# FPGA1_PWR.net
KiCad netlist of a schematic drawn in Altium Designer
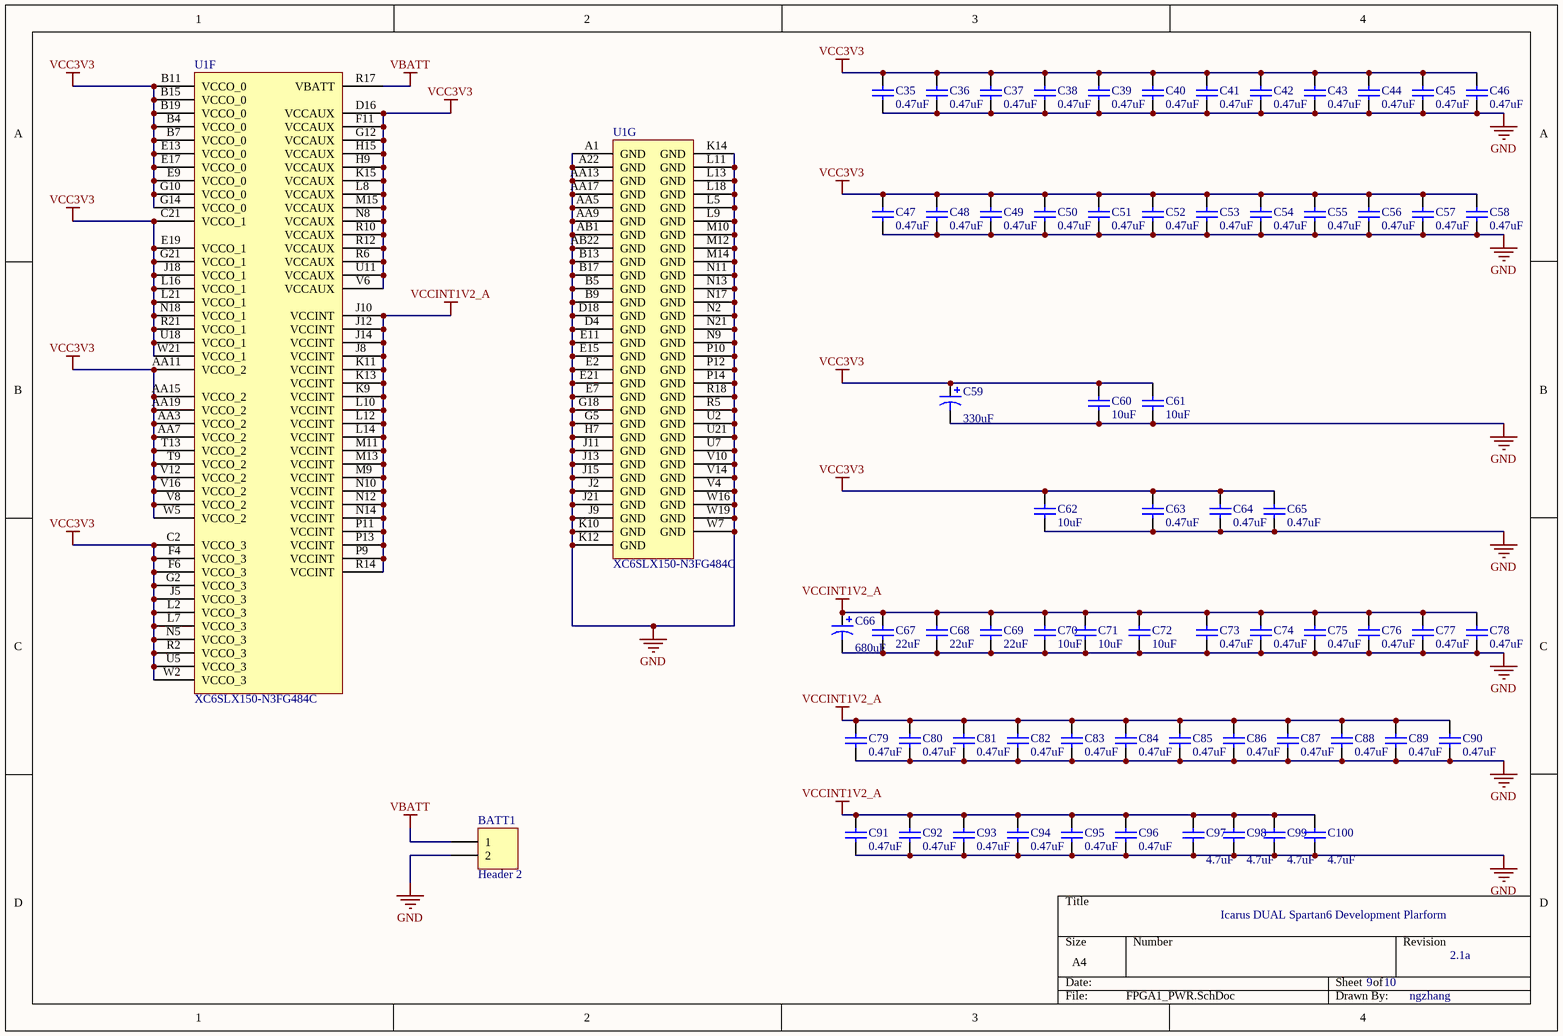
[diagram p0: FPGA1_PWR.SchDoc]

(export (version "E")
  (design (tool "Eeschema 10.0.6"))
  (components
    (comp (ref "BATT1")
      (value "Header 2")
      (footprint "HDR1X2")
      (description "Header, 2-Pin")
      (fields (field (name "PUBLISHER") "Altium Limited"))
      (libsource (lib "Miscellaneous Connectors") (part "Header 2"))
    )
    (comp (ref "C35")
      (value "0.47uF")
      (footprint "BGA0402")
      (description "Capacitor (Semiconductor SIM Model)")
      (fields (field (name "PUBLISHER") "Altium Limited"))
      (libsource (lib "Miscellaneous Devices") (part "Cap Semi"))
    )
    (comp (ref "C36")
      (value "0.47uF")
      (footprint "BGA0402")
      (description "Capacitor (Semiconductor SIM Model)")
      (fields (field (name "PUBLISHER") "Altium Limited"))
      (libsource (lib "Miscellaneous Devices") (part "Cap Semi"))
    )
    (comp (ref "C37")
      (value "0.47uF")
      (footprint "BGA0402")
      (description "Capacitor (Semiconductor SIM Model)")
      (fields (field (name "PUBLISHER") "Altium Limited"))
      (libsource (lib "Miscellaneous Devices") (part "Cap Semi"))
    )
    (comp (ref "C38")
      (value "0.47uF")
      (footprint "BGA0402")
      (description "Capacitor (Semiconductor SIM Model)")
      (fields (field (name "PUBLISHER") "Altium Limited"))
      (libsource (lib "Miscellaneous Devices") (part "Cap Semi"))
    )
    (comp (ref "C39")
      (value "0.47uF")
      (footprint "BGA0402")
      (description "Capacitor (Semiconductor SIM Model)")
      (fields (field (name "PUBLISHER") "Altium Limited"))
      (libsource (lib "Miscellaneous Devices") (part "Cap Semi"))
    )
    (comp (ref "C40")
      (value "0.47uF")
      (footprint "BGA0402")
      (description "Capacitor (Semiconductor SIM Model)")
      (fields (field (name "PUBLISHER") "Altium Limited"))
      (libsource (lib "Miscellaneous Devices") (part "Cap Semi"))
    )
    (comp (ref "C41")
      (value "0.47uF")
      (footprint "BGA0402")
      (description "Capacitor (Semiconductor SIM Model)")
      (fields (field (name "PUBLISHER") "Altium Limited"))
      (libsource (lib "Miscellaneous Devices") (part "Cap Semi"))
    )
    (comp (ref "C42")
      (value "0.47uF")
      (footprint "BGA0402")
      (description "Capacitor (Semiconductor SIM Model)")
      (fields (field (name "PUBLISHER") "Altium Limited"))
      (libsource (lib "Miscellaneous Devices") (part "Cap Semi"))
    )
    (comp (ref "C43")
      (value "0.47uF")
      (footprint "BGA0402")
      (description "Capacitor (Semiconductor SIM Model)")
      (fields (field (name "PUBLISHER") "Altium Limited"))
      (libsource (lib "Miscellaneous Devices") (part "Cap Semi"))
    )
    (comp (ref "C44")
      (value "0.47uF")
      (footprint "BGA0402")
      (description "Capacitor (Semiconductor SIM Model)")
      (fields (field (name "PUBLISHER") "Altium Limited"))
      (libsource (lib "Miscellaneous Devices") (part "Cap Semi"))
    )
    (comp (ref "C45")
      (value "0.47uF")
      (footprint "BGA0402")
      (description "Capacitor (Semiconductor SIM Model)")
      (fields (field (name "PUBLISHER") "Altium Limited"))
      (libsource (lib "Miscellaneous Devices") (part "Cap Semi"))
    )
    (comp (ref "C46")
      (value "0.47uF")
      (footprint "BGA0402")
      (description "Capacitor (Semiconductor SIM Model)")
      (fields (field (name "PUBLISHER") "Altium Limited"))
      (libsource (lib "Miscellaneous Devices") (part "Cap Semi"))
    )
    (comp (ref "C47")
      (value "0.47uF")
      (footprint "BGA0402")
      (description "Capacitor (Semiconductor SIM Model)")
      (fields (field (name "PUBLISHER") "Altium Limited"))
      (libsource (lib "Miscellaneous Devices") (part "Cap Semi"))
    )
    (comp (ref "C48")
      (value "0.47uF")
      (footprint "BGA0402")
      (description "Capacitor (Semiconductor SIM Model)")
      (fields (field (name "PUBLISHER") "Altium Limited"))
      (libsource (lib "Miscellaneous Devices") (part "Cap Semi"))
    )
    (comp (ref "C49")
      (value "0.47uF")
      (footprint "BGA0402")
      (description "Capacitor (Semiconductor SIM Model)")
      (fields (field (name "PUBLISHER") "Altium Limited"))
      (libsource (lib "Miscellaneous Devices") (part "Cap Semi"))
    )
    (comp (ref "C50")
      (value "0.47uF")
      (footprint "BGA0402")
      (description "Capacitor (Semiconductor SIM Model)")
      (fields (field (name "PUBLISHER") "Altium Limited"))
      (libsource (lib "Miscellaneous Devices") (part "Cap Semi"))
    )
    (comp (ref "C51")
      (value "0.47uF")
      (footprint "BGA0402")
      (description "Capacitor (Semiconductor SIM Model)")
      (fields (field (name "PUBLISHER") "Altium Limited"))
      (libsource (lib "Miscellaneous Devices") (part "Cap Semi"))
    )
    (comp (ref "C52")
      (value "0.47uF")
      (footprint "BGA0402")
      (description "Capacitor (Semiconductor SIM Model)")
      (fields (field (name "PUBLISHER") "Altium Limited"))
      (libsource (lib "Miscellaneous Devices") (part "Cap Semi"))
    )
    (comp (ref "C53")
      (value "0.47uF")
      (footprint "BGA0402")
      (description "Capacitor (Semiconductor SIM Model)")
      (fields (field (name "PUBLISHER") "Altium Limited"))
      (libsource (lib "Miscellaneous Devices") (part "Cap Semi"))
    )
    (comp (ref "C54")
      (value "0.47uF")
      (footprint "BGA0402")
      (description "Capacitor (Semiconductor SIM Model)")
      (fields (field (name "PUBLISHER") "Altium Limited"))
      (libsource (lib "Miscellaneous Devices") (part "Cap Semi"))
    )
    (comp (ref "C55")
      (value "0.47uF")
      (footprint "BGA0402")
      (description "Capacitor (Semiconductor SIM Model)")
      (fields (field (name "PUBLISHER") "Altium Limited"))
      (libsource (lib "Miscellaneous Devices") (part "Cap Semi"))
    )
    (comp (ref "C56")
      (value "0.47uF")
      (footprint "BGA0402")
      (description "Capacitor (Semiconductor SIM Model)")
      (fields (field (name "PUBLISHER") "Altium Limited"))
      (libsource (lib "Miscellaneous Devices") (part "Cap Semi"))
    )
    (comp (ref "C57")
      (value "0.47uF")
      (footprint "BGA0402")
      (description "Capacitor (Semiconductor SIM Model)")
      (fields (field (name "PUBLISHER") "Altium Limited"))
      (libsource (lib "Miscellaneous Devices") (part "Cap Semi"))
    )
    (comp (ref "C58")
      (value "0.47uF")
      (footprint "BGA0402")
      (description "Capacitor (Semiconductor SIM Model)")
      (fields (field (name "PUBLISHER") "Altium Limited"))
      (libsource (lib "Miscellaneous Devices") (part "Cap Semi"))
    )
    (comp (ref "C59")
      (value "330uF")
      (footprint "D")
      (description "Polarized Capacitor (Surface Mount)")
      (fields (field (name "PUBLISHER") "Altium Limited"))
      (libsource (lib "Miscellaneous Devices") (part "Cap Pol3"))
    )
    (comp (ref "C60")
      (value "10uF")
      (footprint "CAPC2012N")
      (description "Capacitor (Semiconductor SIM Model)")
      (fields (field (name "PUBLISHER") "Altium Limited"))
      (libsource (lib "Miscellaneous Devices") (part "Cap Semi"))
    )
    (comp (ref "C61")
      (value "10uF")
      (footprint "CAPC2012N")
      (description "Capacitor (Semiconductor SIM Model)")
      (fields (field (name "PUBLISHER") "Altium Limited"))
      (libsource (lib "Miscellaneous Devices") (part "Cap Semi"))
    )
    (comp (ref "C62")
      (value "10uF")
      (footprint "CAPC2012N")
      (description "Capacitor (Semiconductor SIM Model)")
      (fields (field (name "PUBLISHER") "Altium Limited"))
      (libsource (lib "Miscellaneous Devices") (part "Cap Semi"))
    )
    (comp (ref "C63")
      (value "0.47uF")
      (footprint "BGA0402")
      (description "Capacitor (Semiconductor SIM Model)")
      (fields (field (name "PUBLISHER") "Altium Limited"))
      (libsource (lib "Miscellaneous Devices") (part "Cap Semi"))
    )
    (comp (ref "C64")
      (value "0.47uF")
      (footprint "BGA0402")
      (description "Capacitor (Semiconductor SIM Model)")
      (fields (field (name "PUBLISHER") "Altium Limited"))
      (libsource (lib "Miscellaneous Devices") (part "Cap Semi"))
    )
    (comp (ref "C65")
      (value "0.47uF")
      (footprint "BGA0402")
      (description "Capacitor (Semiconductor SIM Model)")
      (fields (field (name "PUBLISHER") "Altium Limited"))
      (libsource (lib "Miscellaneous Devices") (part "Cap Semi"))
    )
    (comp (ref "C66")
      (value "680uF")
      (footprint "D")
      (description "Polarized Capacitor (Surface Mount)")
      (fields (field (name "PUBLISHER") "Altium Limited"))
      (libsource (lib "Miscellaneous Devices") (part "Cap Pol3"))
    )
    (comp (ref "C67")
      (value "22uF")
      (footprint "CAPC3216N")
      (description "Capacitor (Semiconductor SIM Model)")
      (fields (field (name "PUBLISHER") "Altium Limited"))
      (libsource (lib "Miscellaneous Devices") (part "Cap Semi"))
    )
    (comp (ref "C68")
      (value "22uF")
      (footprint "CAPC3216N")
      (description "Capacitor (Semiconductor SIM Model)")
      (fields (field (name "PUBLISHER") "Altium Limited"))
      (libsource (lib "Miscellaneous Devices") (part "Cap Semi"))
    )
    (comp (ref "C69")
      (value "22uF")
      (footprint "CAPC3216N")
      (description "Capacitor (Semiconductor SIM Model)")
      (fields (field (name "PUBLISHER") "Altium Limited"))
      (libsource (lib "Miscellaneous Devices") (part "Cap Semi"))
    )
    (comp (ref "C70")
      (value "10uF")
      (footprint "CAPC2012N")
      (description "Capacitor (Semiconductor SIM Model)")
      (fields (field (name "PUBLISHER") "Altium Limited"))
      (libsource (lib "Miscellaneous Devices") (part "Cap Semi"))
    )
    (comp (ref "C71")
      (value "10uF")
      (footprint "CAPC2012N")
      (description "Capacitor (Semiconductor SIM Model)")
      (fields (field (name "PUBLISHER") "Altium Limited"))
      (libsource (lib "Miscellaneous Devices") (part "Cap Semi"))
    )
    (comp (ref "C72")
      (value "10uF")
      (footprint "CAPC2012N")
      (description "Capacitor (Semiconductor SIM Model)")
      (fields (field (name "PUBLISHER") "Altium Limited"))
      (libsource (lib "Miscellaneous Devices") (part "Cap Semi"))
    )
    (comp (ref "C73")
      (value "0.47uF")
      (footprint "BGA0402")
      (description "Capacitor (Semiconductor SIM Model)")
      (fields (field (name "PUBLISHER") "Altium Limited"))
      (libsource (lib "Miscellaneous Devices") (part "Cap Semi"))
    )
    (comp (ref "C74")
      (value "0.47uF")
      (footprint "BGA0402")
      (description "Capacitor (Semiconductor SIM Model)")
      (fields (field (name "PUBLISHER") "Altium Limited"))
      (libsource (lib "Miscellaneous Devices") (part "Cap Semi"))
    )
    (comp (ref "C75")
      (value "0.47uF")
      (footprint "BGA0402")
      (description "Capacitor (Semiconductor SIM Model)")
      (fields (field (name "PUBLISHER") "Altium Limited"))
      (libsource (lib "Miscellaneous Devices") (part "Cap Semi"))
    )
    (comp (ref "C76")
      (value "0.47uF")
      (footprint "BGA0402")
      (description "Capacitor (Semiconductor SIM Model)")
      (fields (field (name "PUBLISHER") "Altium Limited"))
      (libsource (lib "Miscellaneous Devices") (part "Cap Semi"))
    )
    (comp (ref "C77")
      (value "0.47uF")
      (footprint "BGA0402")
      (description "Capacitor (Semiconductor SIM Model)")
      (fields (field (name "PUBLISHER") "Altium Limited"))
      (libsource (lib "Miscellaneous Devices") (part "Cap Semi"))
    )
    (comp (ref "C78")
      (value "0.47uF")
      (footprint "BGA0402")
      (description "Capacitor (Semiconductor SIM Model)")
      (fields (field (name "PUBLISHER") "Altium Limited"))
      (libsource (lib "Miscellaneous Devices") (part "Cap Semi"))
    )
    (comp (ref "C79")
      (value "0.47uF")
      (footprint "BGA0402")
      (description "Capacitor (Semiconductor SIM Model)")
      (fields (field (name "PUBLISHER") "Altium Limited"))
      (libsource (lib "Miscellaneous Devices") (part "Cap Semi"))
    )
    (comp (ref "C80")
      (value "0.47uF")
      (footprint "BGA0402")
      (description "Capacitor (Semiconductor SIM Model)")
      (fields (field (name "PUBLISHER") "Altium Limited"))
      (libsource (lib "Miscellaneous Devices") (part "Cap Semi"))
    )
    (comp (ref "C81")
      (value "0.47uF")
      (footprint "BGA0402")
      (description "Capacitor (Semiconductor SIM Model)")
      (fields (field (name "PUBLISHER") "Altium Limited"))
      (libsource (lib "Miscellaneous Devices") (part "Cap Semi"))
    )
    (comp (ref "C82")
      (value "0.47uF")
      (footprint "BGA0402")
      (description "Capacitor (Semiconductor SIM Model)")
      (fields (field (name "PUBLISHER") "Altium Limited"))
      (libsource (lib "Miscellaneous Devices") (part "Cap Semi"))
    )
    (comp (ref "C83")
      (value "0.47uF")
      (footprint "BGA0402")
      (description "Capacitor (Semiconductor SIM Model)")
      (fields (field (name "PUBLISHER") "Altium Limited"))
      (libsource (lib "Miscellaneous Devices") (part "Cap Semi"))
    )
    (comp (ref "C84")
      (value "0.47uF")
      (footprint "BGA0402")
      (description "Capacitor (Semiconductor SIM Model)")
      (fields (field (name "PUBLISHER") "Altium Limited"))
      (libsource (lib "Miscellaneous Devices") (part "Cap Semi"))
    )
    (comp (ref "C85")
      (value "0.47uF")
      (footprint "BGA0402")
      (description "Capacitor (Semiconductor SIM Model)")
      (fields (field (name "PUBLISHER") "Altium Limited"))
      (libsource (lib "Miscellaneous Devices") (part "Cap Semi"))
    )
    (comp (ref "C86")
      (value "0.47uF")
      (footprint "BGA0402")
      (description "Capacitor (Semiconductor SIM Model)")
      (fields (field (name "PUBLISHER") "Altium Limited"))
      (libsource (lib "Miscellaneous Devices") (part "Cap Semi"))
    )
    (comp (ref "C87")
      (value "0.47uF")
      (footprint "BGA0402")
      (description "Capacitor (Semiconductor SIM Model)")
      (fields (field (name "PUBLISHER") "Altium Limited"))
      (libsource (lib "Miscellaneous Devices") (part "Cap Semi"))
    )
    (comp (ref "C88")
      (value "0.47uF")
      (footprint "BGA0402")
      (description "Capacitor (Semiconductor SIM Model)")
      (fields (field (name "PUBLISHER") "Altium Limited"))
      (libsource (lib "Miscellaneous Devices") (part "Cap Semi"))
    )
    (comp (ref "C89")
      (value "0.47uF")
      (footprint "BGA0402")
      (description "Capacitor (Semiconductor SIM Model)")
      (fields (field (name "PUBLISHER") "Altium Limited"))
      (libsource (lib "Miscellaneous Devices") (part "Cap Semi"))
    )
    (comp (ref "C90")
      (value "0.47uF")
      (footprint "BGA0402")
      (description "Capacitor (Semiconductor SIM Model)")
      (fields (field (name "PUBLISHER") "Altium Limited"))
      (libsource (lib "Miscellaneous Devices") (part "Cap Semi"))
    )
    (comp (ref "C91")
      (value "0.47uF")
      (footprint "BGA0402")
      (description "Capacitor (Semiconductor SIM Model)")
      (fields (field (name "PUBLISHER") "Altium Limited"))
      (libsource (lib "Miscellaneous Devices") (part "Cap Semi"))
    )
    (comp (ref "C92")
      (value "0.47uF")
      (footprint "BGA0402")
      (description "Capacitor (Semiconductor SIM Model)")
      (fields (field (name "PUBLISHER") "Altium Limited"))
      (libsource (lib "Miscellaneous Devices") (part "Cap Semi"))
    )
    (comp (ref "C93")
      (value "0.47uF")
      (footprint "BGA0402")
      (description "Capacitor (Semiconductor SIM Model)")
      (fields (field (name "PUBLISHER") "Altium Limited"))
      (libsource (lib "Miscellaneous Devices") (part "Cap Semi"))
    )
    (comp (ref "C94")
      (value "0.47uF")
      (footprint "BGA0402")
      (description "Capacitor (Semiconductor SIM Model)")
      (fields (field (name "PUBLISHER") "Altium Limited"))
      (libsource (lib "Miscellaneous Devices") (part "Cap Semi"))
    )
    (comp (ref "C95")
      (value "0.47uF")
      (footprint "BGA0402")
      (description "Capacitor (Semiconductor SIM Model)")
      (fields (field (name "PUBLISHER") "Altium Limited"))
      (libsource (lib "Miscellaneous Devices") (part "Cap Semi"))
    )
    (comp (ref "C96")
      (value "0.47uF")
      (footprint "BGA0402")
      (description "Capacitor (Semiconductor SIM Model)")
      (fields (field (name "PUBLISHER") "Altium Limited"))
      (libsource (lib "Miscellaneous Devices") (part "Cap Semi"))
    )
    (comp (ref "C97")
      (value "4.7uF")
      (footprint "CAPC1608N")
      (description "Capacitor (Semiconductor SIM Model)")
      (fields (field (name "PUBLISHER") "Altium Limited"))
      (libsource (lib "Miscellaneous Devices") (part "Cap Semi"))
    )
    (comp (ref "C98")
      (value "4.7uF")
      (footprint "CAPC1608N")
      (description "Capacitor (Semiconductor SIM Model)")
      (fields (field (name "PUBLISHER") "Altium Limited"))
      (libsource (lib "Miscellaneous Devices") (part "Cap Semi"))
    )
    (comp (ref "C99")
      (value "4.7uF")
      (footprint "CAPC1608N")
      (description "Capacitor (Semiconductor SIM Model)")
      (fields (field (name "PUBLISHER") "Altium Limited"))
      (libsource (lib "Miscellaneous Devices") (part "Cap Semi"))
    )
    (comp (ref "C100")
      (value "4.7uF")
      (footprint "CAPC1608N")
      (description "Capacitor (Semiconductor SIM Model)")
      (fields (field (name "PUBLISHER") "Altium Limited"))
      (libsource (lib "Miscellaneous Devices") (part "Cap Semi"))
    )
    (comp (ref "U1")
      (value "XC6SLX150-N3FG484C")
      (footprint "FG484")
      (fields (field (name "PUBLISHER") "Altium Limited"))
      (libsource (lib "Xilinx Spartan-6") (part "XC6SLX150-N3FG484C"))
    )
  )
  (nets
    (net (code "1") (name "GND") (class "Default")
      (node (ref "BATT1") (pin "2") (pinfunction "2_2") (pintype "passive"))
      (node (ref "C100") (pin "1") (pinfunction "1_1") (pintype "passive"))
      (node (ref "C35") (pin "1") (pinfunction "1_1") (pintype "passive"))
      (node (ref "C36") (pin "1") (pinfunction "1_1") (pintype "passive"))
      (node (ref "C37") (pin "1") (pinfunction "1_1") (pintype "passive"))
      (node (ref "C38") (pin "1") (pinfunction "1_1") (pintype "passive"))
      (node (ref "C39") (pin "1") (pinfunction "1_1") (pintype "passive"))
      (node (ref "C40") (pin "1") (pinfunction "1_1") (pintype "passive"))
      (node (ref "C41") (pin "1") (pinfunction "1_1") (pintype "passive"))
      (node (ref "C42") (pin "1") (pinfunction "1_1") (pintype "passive"))
      (node (ref "C43") (pin "1") (pinfunction "1_1") (pintype "passive"))
      (node (ref "C44") (pin "1") (pinfunction "1_1") (pintype "passive"))
      (node (ref "C45") (pin "1") (pinfunction "1_1") (pintype "passive"))
      (node (ref "C46") (pin "1") (pinfunction "1_1") (pintype "passive"))
      (node (ref "C47") (pin "1") (pinfunction "1_1") (pintype "passive"))
      (node (ref "C48") (pin "1") (pinfunction "1_1") (pintype "passive"))
      (node (ref "C49") (pin "1") (pinfunction "1_1") (pintype "passive"))
      (node (ref "C50") (pin "1") (pinfunction "1_1") (pintype "passive"))
      (node (ref "C51") (pin "1") (pinfunction "1_1") (pintype "passive"))
      (node (ref "C52") (pin "1") (pinfunction "1_1") (pintype "passive"))
      (node (ref "C53") (pin "1") (pinfunction "1_1") (pintype "passive"))
      (node (ref "C54") (pin "1") (pinfunction "1_1") (pintype "passive"))
      (node (ref "C55") (pin "1") (pinfunction "1_1") (pintype "passive"))
      (node (ref "C56") (pin "1") (pinfunction "1_1") (pintype "passive"))
      (node (ref "C57") (pin "1") (pinfunction "1_1") (pintype "passive"))
      (node (ref "C58") (pin "1") (pinfunction "1_1") (pintype "passive"))
      (node (ref "C59") (pin "2") (pinfunction "2_2") (pintype "passive"))
      (node (ref "C60") (pin "1") (pinfunction "1_1") (pintype "passive"))
      (node (ref "C61") (pin "1") (pinfunction "1_1") (pintype "passive"))
      (node (ref "C62") (pin "1") (pinfunction "1_1") (pintype "passive"))
      (node (ref "C63") (pin "1") (pinfunction "1_1") (pintype "passive"))
      (node (ref "C64") (pin "1") (pinfunction "1_1") (pintype "passive"))
      (node (ref "C65") (pin "1") (pinfunction "1_1") (pintype "passive"))
      (node (ref "C66") (pin "2") (pinfunction "2_2") (pintype "passive"))
      (node (ref "C67") (pin "1") (pinfunction "1_1") (pintype "passive"))
      (node (ref "C68") (pin "1") (pinfunction "1_1") (pintype "passive"))
      (node (ref "C69") (pin "1") (pinfunction "1_1") (pintype "passive"))
      (node (ref "C70") (pin "1") (pinfunction "1_1") (pintype "passive"))
      (node (ref "C71") (pin "1") (pinfunction "1_1") (pintype "passive"))
      (node (ref "C72") (pin "1") (pinfunction "1_1") (pintype "passive"))
      (node (ref "C73") (pin "1") (pinfunction "1_1") (pintype "passive"))
      (node (ref "C74") (pin "1") (pinfunction "1_1") (pintype "passive"))
      (node (ref "C75") (pin "1") (pinfunction "1_1") (pintype "passive"))
      (node (ref "C76") (pin "1") (pinfunction "1_1") (pintype "passive"))
      (node (ref "C77") (pin "1") (pinfunction "1_1") (pintype "passive"))
      (node (ref "C78") (pin "1") (pinfunction "1_1") (pintype "passive"))
      (node (ref "C79") (pin "1") (pinfunction "1_1") (pintype "passive"))
      (node (ref "C80") (pin "1") (pinfunction "1_1") (pintype "passive"))
      (node (ref "C81") (pin "1") (pinfunction "1_1") (pintype "passive"))
      (node (ref "C82") (pin "1") (pinfunction "1_1") (pintype "passive"))
      (node (ref "C83") (pin "1") (pinfunction "1_1") (pintype "passive"))
      (node (ref "C84") (pin "1") (pinfunction "1_1") (pintype "passive"))
      (node (ref "C85") (pin "1") (pinfunction "1_1") (pintype "passive"))
      (node (ref "C86") (pin "1") (pinfunction "1_1") (pintype "passive"))
      (node (ref "C87") (pin "1") (pinfunction "1_1") (pintype "passive"))
      (node (ref "C88") (pin "1") (pinfunction "1_1") (pintype "passive"))
      (node (ref "C89") (pin "1") (pinfunction "1_1") (pintype "passive"))
      (node (ref "C90") (pin "1") (pinfunction "1_1") (pintype "passive"))
      (node (ref "C91") (pin "1") (pinfunction "1_1") (pintype "passive"))
      (node (ref "C92") (pin "1") (pinfunction "1_1") (pintype "passive"))
      (node (ref "C93") (pin "1") (pinfunction "1_1") (pintype "passive"))
      (node (ref "C94") (pin "1") (pinfunction "1_1") (pintype "passive"))
      (node (ref "C95") (pin "1") (pinfunction "1_1") (pintype "passive"))
      (node (ref "C96") (pin "1") (pinfunction "1_1") (pintype "passive"))
      (node (ref "C97") (pin "1") (pinfunction "1_1") (pintype "passive"))
      (node (ref "C98") (pin "1") (pinfunction "1_1") (pintype "passive"))
      (node (ref "C99") (pin "1") (pinfunction "1_1") (pintype "passive"))
      (node (ref "U1") (pin "A1") (pinfunction "GND_A1") (pintype "power_in"))
      (node (ref "U1") (pin "A22") (pinfunction "GND_A22") (pintype "power_in"))
      (node (ref "U1") (pin "AA13") (pinfunction "GND_AA13") (pintype "power_in"))
      (node (ref "U1") (pin "AA17") (pinfunction "GND_AA17") (pintype "power_in"))
      (node (ref "U1") (pin "AA5") (pinfunction "GND_AA5") (pintype "power_in"))
      (node (ref "U1") (pin "AA9") (pinfunction "GND_AA9") (pintype "power_in"))
      (node (ref "U1") (pin "AB1") (pinfunction "GND_AB1") (pintype "power_in"))
      (node (ref "U1") (pin "AB22") (pinfunction "GND_AB22") (pintype "power_in"))
      (node (ref "U1") (pin "B13") (pinfunction "GND_B13") (pintype "power_in"))
      (node (ref "U1") (pin "B17") (pinfunction "GND_B17") (pintype "power_in"))
      (node (ref "U1") (pin "B5") (pinfunction "GND_B5") (pintype "power_in"))
      (node (ref "U1") (pin "B9") (pinfunction "GND_B9") (pintype "power_in"))
      (node (ref "U1") (pin "D18") (pinfunction "GND_D18") (pintype "power_in"))
      (node (ref "U1") (pin "D4") (pinfunction "GND_D4") (pintype "power_in"))
      (node (ref "U1") (pin "E11") (pinfunction "GND_E11") (pintype "power_in"))
      (node (ref "U1") (pin "E15") (pinfunction "GND_E15") (pintype "power_in"))
      (node (ref "U1") (pin "E2") (pinfunction "GND_E2") (pintype "power_in"))
      (node (ref "U1") (pin "E21") (pinfunction "GND_E21") (pintype "power_in"))
      (node (ref "U1") (pin "E7") (pinfunction "GND_E7") (pintype "power_in"))
      (node (ref "U1") (pin "G18") (pinfunction "GND_G18") (pintype "power_in"))
      (node (ref "U1") (pin "G5") (pinfunction "GND_G5") (pintype "power_in"))
      (node (ref "U1") (pin "H7") (pinfunction "GND_H7") (pintype "power_in"))
      (node (ref "U1") (pin "J11") (pinfunction "GND_J11") (pintype "power_in"))
      (node (ref "U1") (pin "J13") (pinfunction "GND_J13") (pintype "power_in"))
      (node (ref "U1") (pin "J15") (pinfunction "GND_J15") (pintype "power_in"))
      (node (ref "U1") (pin "J2") (pinfunction "GND_J2") (pintype "power_in"))
      (node (ref "U1") (pin "J21") (pinfunction "GND_J21") (pintype "power_in"))
      (node (ref "U1") (pin "J9") (pinfunction "GND_J9") (pintype "power_in"))
      (node (ref "U1") (pin "K10") (pinfunction "GND_K10") (pintype "power_in"))
      (node (ref "U1") (pin "K12") (pinfunction "GND_K12") (pintype "power_in"))
      (node (ref "U1") (pin "K14") (pinfunction "GND_K14") (pintype "power_in"))
      (node (ref "U1") (pin "L11") (pinfunction "GND_L11") (pintype "power_in"))
      (node (ref "U1") (pin "L13") (pinfunction "GND_L13") (pintype "power_in"))
      (node (ref "U1") (pin "L18") (pinfunction "GND_L18") (pintype "power_in"))
      (node (ref "U1") (pin "L5") (pinfunction "GND_L5") (pintype "power_in"))
      (node (ref "U1") (pin "L9") (pinfunction "GND_L9") (pintype "power_in"))
      (node (ref "U1") (pin "M10") (pinfunction "GND_M10") (pintype "power_in"))
      (node (ref "U1") (pin "M12") (pinfunction "GND_M12") (pintype "power_in"))
      (node (ref "U1") (pin "M14") (pinfunction "GND_M14") (pintype "power_in"))
      (node (ref "U1") (pin "N11") (pinfunction "GND_N11") (pintype "power_in"))
      (node (ref "U1") (pin "N13") (pinfunction "GND_N13") (pintype "power_in"))
      (node (ref "U1") (pin "N17") (pinfunction "GND_N17") (pintype "power_in"))
      (node (ref "U1") (pin "N2") (pinfunction "GND_N2") (pintype "power_in"))
      (node (ref "U1") (pin "N21") (pinfunction "GND_N21") (pintype "power_in"))
      (node (ref "U1") (pin "N9") (pinfunction "GND_N9") (pintype "power_in"))
      (node (ref "U1") (pin "P10") (pinfunction "GND_P10") (pintype "power_in"))
      (node (ref "U1") (pin "P12") (pinfunction "GND_P12") (pintype "power_in"))
      (node (ref "U1") (pin "P14") (pinfunction "GND_P14") (pintype "power_in"))
      (node (ref "U1") (pin "R18") (pinfunction "GND_R18") (pintype "power_in"))
      (node (ref "U1") (pin "R5") (pinfunction "GND_R5") (pintype "power_in"))
      (node (ref "U1") (pin "U2") (pinfunction "GND_U2") (pintype "power_in"))
      (node (ref "U1") (pin "U21") (pinfunction "GND_U21") (pintype "power_in"))
      (node (ref "U1") (pin "U7") (pinfunction "GND_U7") (pintype "power_in"))
      (node (ref "U1") (pin "V10") (pinfunction "GND_V10") (pintype "power_in"))
      (node (ref "U1") (pin "V14") (pinfunction "GND_V14") (pintype "power_in"))
      (node (ref "U1") (pin "V4") (pinfunction "GND_V4") (pintype "power_in"))
      (node (ref "U1") (pin "W16") (pinfunction "GND_W16") (pintype "power_in"))
      (node (ref "U1") (pin "W19") (pinfunction "GND_W19") (pintype "power_in"))
      (node (ref "U1") (pin "W7") (pinfunction "GND_W7") (pintype "power_in"))
    )
    (net (code "2") (name "VBATT") (class "Default")
      (node (ref "BATT1") (pin "1") (pinfunction "1_1") (pintype "passive"))
      (node (ref "U1") (pin "R17") (pinfunction "VBATT_R17") (pintype "power_in"))
    )
    (net (code "3") (name "VCC3V3") (class "Default")
      (node (ref "C35") (pin "2") (pinfunction "2_2") (pintype "passive"))
      (node (ref "C36") (pin "2") (pinfunction "2_2") (pintype "passive"))
      (node (ref "C37") (pin "2") (pinfunction "2_2") (pintype "passive"))
      (node (ref "C38") (pin "2") (pinfunction "2_2") (pintype "passive"))
      (node (ref "C39") (pin "2") (pinfunction "2_2") (pintype "passive"))
      (node (ref "C40") (pin "2") (pinfunction "2_2") (pintype "passive"))
      (node (ref "C41") (pin "2") (pinfunction "2_2") (pintype "passive"))
      (node (ref "C42") (pin "2") (pinfunction "2_2") (pintype "passive"))
      (node (ref "C43") (pin "2") (pinfunction "2_2") (pintype "passive"))
      (node (ref "C44") (pin "2") (pinfunction "2_2") (pintype "passive"))
      (node (ref "C45") (pin "2") (pinfunction "2_2") (pintype "passive"))
      (node (ref "C46") (pin "2") (pinfunction "2_2") (pintype "passive"))
      (node (ref "C47") (pin "2") (pinfunction "2_2") (pintype "passive"))
      (node (ref "C48") (pin "2") (pinfunction "2_2") (pintype "passive"))
      (node (ref "C49") (pin "2") (pinfunction "2_2") (pintype "passive"))
      (node (ref "C50") (pin "2") (pinfunction "2_2") (pintype "passive"))
      (node (ref "C51") (pin "2") (pinfunction "2_2") (pintype "passive"))
      (node (ref "C52") (pin "2") (pinfunction "2_2") (pintype "passive"))
      (node (ref "C53") (pin "2") (pinfunction "2_2") (pintype "passive"))
      (node (ref "C54") (pin "2") (pinfunction "2_2") (pintype "passive"))
      (node (ref "C55") (pin "2") (pinfunction "2_2") (pintype "passive"))
      (node (ref "C56") (pin "2") (pinfunction "2_2") (pintype "passive"))
      (node (ref "C57") (pin "2") (pinfunction "2_2") (pintype "passive"))
      (node (ref "C58") (pin "2") (pinfunction "2_2") (pintype "passive"))
      (node (ref "C59") (pin "1") (pinfunction "1_1") (pintype "passive"))
      (node (ref "C60") (pin "2") (pinfunction "2_2") (pintype "passive"))
      (node (ref "C61") (pin "2") (pinfunction "2_2") (pintype "passive"))
      (node (ref "C62") (pin "2") (pinfunction "2_2") (pintype "passive"))
      (node (ref "C63") (pin "2") (pinfunction "2_2") (pintype "passive"))
      (node (ref "C64") (pin "2") (pinfunction "2_2") (pintype "passive"))
      (node (ref "C65") (pin "2") (pinfunction "2_2") (pintype "passive"))
      (node (ref "U1") (pin "AA11") (pinfunction "VCCO_2_AA11") (pintype "power_in"))
      (node (ref "U1") (pin "AA15") (pinfunction "VCCO_2_AA15") (pintype "power_in"))
      (node (ref "U1") (pin "AA19") (pinfunction "VCCO_2_AA19") (pintype "power_in"))
      (node (ref "U1") (pin "AA3") (pinfunction "VCCO_2_AA3") (pintype "power_in"))
      (node (ref "U1") (pin "AA7") (pinfunction "VCCO_2_AA7") (pintype "power_in"))
      (node (ref "U1") (pin "B11") (pinfunction "VCCO_0_B11") (pintype "power_in"))
      (node (ref "U1") (pin "B15") (pinfunction "VCCO_0_B15") (pintype "power_in"))
      (node (ref "U1") (pin "B19") (pinfunction "VCCO_0_B19") (pintype "power_in"))
      (node (ref "U1") (pin "B4") (pinfunction "VCCO_0_B4") (pintype "power_in"))
      (node (ref "U1") (pin "B7") (pinfunction "VCCO_0_B7") (pintype "power_in"))
      (node (ref "U1") (pin "C2") (pinfunction "VCCO_3_C2") (pintype "power_in"))
      (node (ref "U1") (pin "C21") (pinfunction "VCCO_1_C21") (pintype "power_in"))
      (node (ref "U1") (pin "D16") (pinfunction "VCCAUX_D16") (pintype "power_in"))
      (node (ref "U1") (pin "E13") (pinfunction "VCCO_0_E13") (pintype "power_in"))
      (node (ref "U1") (pin "E17") (pinfunction "VCCO_0_E17") (pintype "power_in"))
      (node (ref "U1") (pin "E19") (pinfunction "VCCO_1_E19") (pintype "power_in"))
      (node (ref "U1") (pin "E9") (pinfunction "VCCO_0_E9") (pintype "power_in"))
      (node (ref "U1") (pin "F11") (pinfunction "VCCAUX_F11") (pintype "power_in"))
      (node (ref "U1") (pin "F4") (pinfunction "VCCO_3_F4") (pintype "power_in"))
      (node (ref "U1") (pin "F6") (pinfunction "VCCO_3_F6") (pintype "power_in"))
      (node (ref "U1") (pin "G10") (pinfunction "VCCO_0_G10") (pintype "power_in"))
      (node (ref "U1") (pin "G12") (pinfunction "VCCAUX_G12") (pintype "power_in"))
      (node (ref "U1") (pin "G14") (pinfunction "VCCO_0_G14") (pintype "power_in"))
      (node (ref "U1") (pin "G2") (pinfunction "VCCO_3_G2") (pintype "power_in"))
      (node (ref "U1") (pin "G21") (pinfunction "VCCO_1_G21") (pintype "power_in"))
      (node (ref "U1") (pin "H15") (pinfunction "VCCAUX_H15") (pintype "power_in"))
      (node (ref "U1") (pin "H9") (pinfunction "VCCAUX_H9") (pintype "power_in"))
      (node (ref "U1") (pin "J18") (pinfunction "VCCO_1_J18") (pintype "power_in"))
      (node (ref "U1") (pin "J5") (pinfunction "VCCO_3_J5") (pintype "power_in"))
      (node (ref "U1") (pin "K15") (pinfunction "VCCAUX_K15") (pintype "power_in"))
      (node (ref "U1") (pin "L16") (pinfunction "VCCO_1_L16") (pintype "power_in"))
      (node (ref "U1") (pin "L2") (pinfunction "VCCO_3_L2") (pintype "power_in"))
      (node (ref "U1") (pin "L21") (pinfunction "VCCO_1_L21") (pintype "power_in"))
      (node (ref "U1") (pin "L7") (pinfunction "VCCO_3_L7") (pintype "power_in"))
      (node (ref "U1") (pin "L8") (pinfunction "VCCAUX_L8") (pintype "power_in"))
      (node (ref "U1") (pin "M15") (pinfunction "VCCAUX_M15") (pintype "power_in"))
      (node (ref "U1") (pin "N18") (pinfunction "VCCO_1_N18") (pintype "power_in"))
      (node (ref "U1") (pin "N5") (pinfunction "VCCO_3_N5") (pintype "power_in"))
      (node (ref "U1") (pin "N8") (pinfunction "VCCAUX_N8") (pintype "power_in"))
      (node (ref "U1") (pin "R10") (pinfunction "VCCAUX_R10") (pintype "power_in"))
      (node (ref "U1") (pin "R12") (pinfunction "VCCAUX_R12") (pintype "power_in"))
      (node (ref "U1") (pin "R2") (pinfunction "VCCO_3_R2") (pintype "power_in"))
      (node (ref "U1") (pin "R21") (pinfunction "VCCO_1_R21") (pintype "power_in"))
      (node (ref "U1") (pin "R6") (pinfunction "VCCAUX_R6") (pintype "power_in"))
      (node (ref "U1") (pin "T13") (pinfunction "VCCO_2_T13") (pintype "power_in"))
      (node (ref "U1") (pin "T9") (pinfunction "VCCO_2_T9") (pintype "power_in"))
      (node (ref "U1") (pin "U11") (pinfunction "VCCAUX_U11") (pintype "power_in"))
      (node (ref "U1") (pin "U18") (pinfunction "VCCO_1_U18") (pintype "power_in"))
      (node (ref "U1") (pin "U5") (pinfunction "VCCO_3_U5") (pintype "power_in"))
      (node (ref "U1") (pin "V12") (pinfunction "VCCO_2_V12") (pintype "power_in"))
      (node (ref "U1") (pin "V16") (pinfunction "VCCO_2_V16") (pintype "power_in"))
      (node (ref "U1") (pin "V6") (pinfunction "VCCAUX_V6") (pintype "power_in"))
      (node (ref "U1") (pin "V8") (pinfunction "VCCO_2_V8") (pintype "power_in"))
      (node (ref "U1") (pin "W2") (pinfunction "VCCO_3_W2") (pintype "power_in"))
      (node (ref "U1") (pin "W21") (pinfunction "VCCO_1_W21") (pintype "power_in"))
      (node (ref "U1") (pin "W5") (pinfunction "VCCO_2_W5") (pintype "power_in"))
    )
    (net (code "4") (name "VCCINT1V2_A") (class "Default")
      (node (ref "C100") (pin "2") (pinfunction "2_2") (pintype "passive"))
      (node (ref "C66") (pin "1") (pinfunction "1_1") (pintype "passive"))
      (node (ref "C67") (pin "2") (pinfunction "2_2") (pintype "passive"))
      (node (ref "C68") (pin "2") (pinfunction "2_2") (pintype "passive"))
      (node (ref "C69") (pin "2") (pinfunction "2_2") (pintype "passive"))
      (node (ref "C70") (pin "2") (pinfunction "2_2") (pintype "passive"))
      (node (ref "C71") (pin "2") (pinfunction "2_2") (pintype "passive"))
      (node (ref "C72") (pin "2") (pinfunction "2_2") (pintype "passive"))
      (node (ref "C73") (pin "2") (pinfunction "2_2") (pintype "passive"))
      (node (ref "C74") (pin "2") (pinfunction "2_2") (pintype "passive"))
      (node (ref "C75") (pin "2") (pinfunction "2_2") (pintype "passive"))
      (node (ref "C76") (pin "2") (pinfunction "2_2") (pintype "passive"))
      (node (ref "C77") (pin "2") (pinfunction "2_2") (pintype "passive"))
      (node (ref "C78") (pin "2") (pinfunction "2_2") (pintype "passive"))
      (node (ref "C79") (pin "2") (pinfunction "2_2") (pintype "passive"))
      (node (ref "C80") (pin "2") (pinfunction "2_2") (pintype "passive"))
      (node (ref "C81") (pin "2") (pinfunction "2_2") (pintype "passive"))
      (node (ref "C82") (pin "2") (pinfunction "2_2") (pintype "passive"))
      (node (ref "C83") (pin "2") (pinfunction "2_2") (pintype "passive"))
      (node (ref "C84") (pin "2") (pinfunction "2_2") (pintype "passive"))
      (node (ref "C85") (pin "2") (pinfunction "2_2") (pintype "passive"))
      (node (ref "C86") (pin "2") (pinfunction "2_2") (pintype "passive"))
      (node (ref "C87") (pin "2") (pinfunction "2_2") (pintype "passive"))
      (node (ref "C88") (pin "2") (pinfunction "2_2") (pintype "passive"))
      (node (ref "C89") (pin "2") (pinfunction "2_2") (pintype "passive"))
      (node (ref "C90") (pin "2") (pinfunction "2_2") (pintype "passive"))
      (node (ref "C91") (pin "2") (pinfunction "2_2") (pintype "passive"))
      (node (ref "C92") (pin "2") (pinfunction "2_2") (pintype "passive"))
      (node (ref "C93") (pin "2") (pinfunction "2_2") (pintype "passive"))
      (node (ref "C94") (pin "2") (pinfunction "2_2") (pintype "passive"))
      (node (ref "C95") (pin "2") (pinfunction "2_2") (pintype "passive"))
      (node (ref "C96") (pin "2") (pinfunction "2_2") (pintype "passive"))
      (node (ref "C97") (pin "2") (pinfunction "2_2") (pintype "passive"))
      (node (ref "C98") (pin "2") (pinfunction "2_2") (pintype "passive"))
      (node (ref "C99") (pin "2") (pinfunction "2_2") (pintype "passive"))
      (node (ref "U1") (pin "J10") (pinfunction "VCCINT_J10") (pintype "power_in"))
      (node (ref "U1") (pin "J12") (pinfunction "VCCINT_J12") (pintype "power_in"))
      (node (ref "U1") (pin "J14") (pinfunction "VCCINT_J14") (pintype "power_in"))
      (node (ref "U1") (pin "J8") (pinfunction "VCCINT_J8") (pintype "power_in"))
      (node (ref "U1") (pin "K11") (pinfunction "VCCINT_K11") (pintype "power_in"))
      (node (ref "U1") (pin "K13") (pinfunction "VCCINT_K13") (pintype "power_in"))
      (node (ref "U1") (pin "K9") (pinfunction "VCCINT_K9") (pintype "power_in"))
      (node (ref "U1") (pin "L10") (pinfunction "VCCINT_L10") (pintype "power_in"))
      (node (ref "U1") (pin "L12") (pinfunction "VCCINT_L12") (pintype "power_in"))
      (node (ref "U1") (pin "L14") (pinfunction "VCCINT_L14") (pintype "power_in"))
      (node (ref "U1") (pin "M11") (pinfunction "VCCINT_M11") (pintype "power_in"))
      (node (ref "U1") (pin "M13") (pinfunction "VCCINT_M13") (pintype "power_in"))
      (node (ref "U1") (pin "M9") (pinfunction "VCCINT_M9") (pintype "power_in"))
      (node (ref "U1") (pin "N10") (pinfunction "VCCINT_N10") (pintype "power_in"))
      (node (ref "U1") (pin "N12") (pinfunction "VCCINT_N12") (pintype "power_in"))
      (node (ref "U1") (pin "N14") (pinfunction "VCCINT_N14") (pintype "power_in"))
      (node (ref "U1") (pin "P11") (pinfunction "VCCINT_P11") (pintype "power_in"))
      (node (ref "U1") (pin "P13") (pinfunction "VCCINT_P13") (pintype "power_in"))
      (node (ref "U1") (pin "P9") (pinfunction "VCCINT_P9") (pintype "power_in"))
      (node (ref "U1") (pin "R14") (pinfunction "VCCINT_R14") (pintype "power_in"))
    )
  )
)
